# Tractive_System_Active_Light_rev5.net
KiCad netlist of a schematic drawn in EAGLE
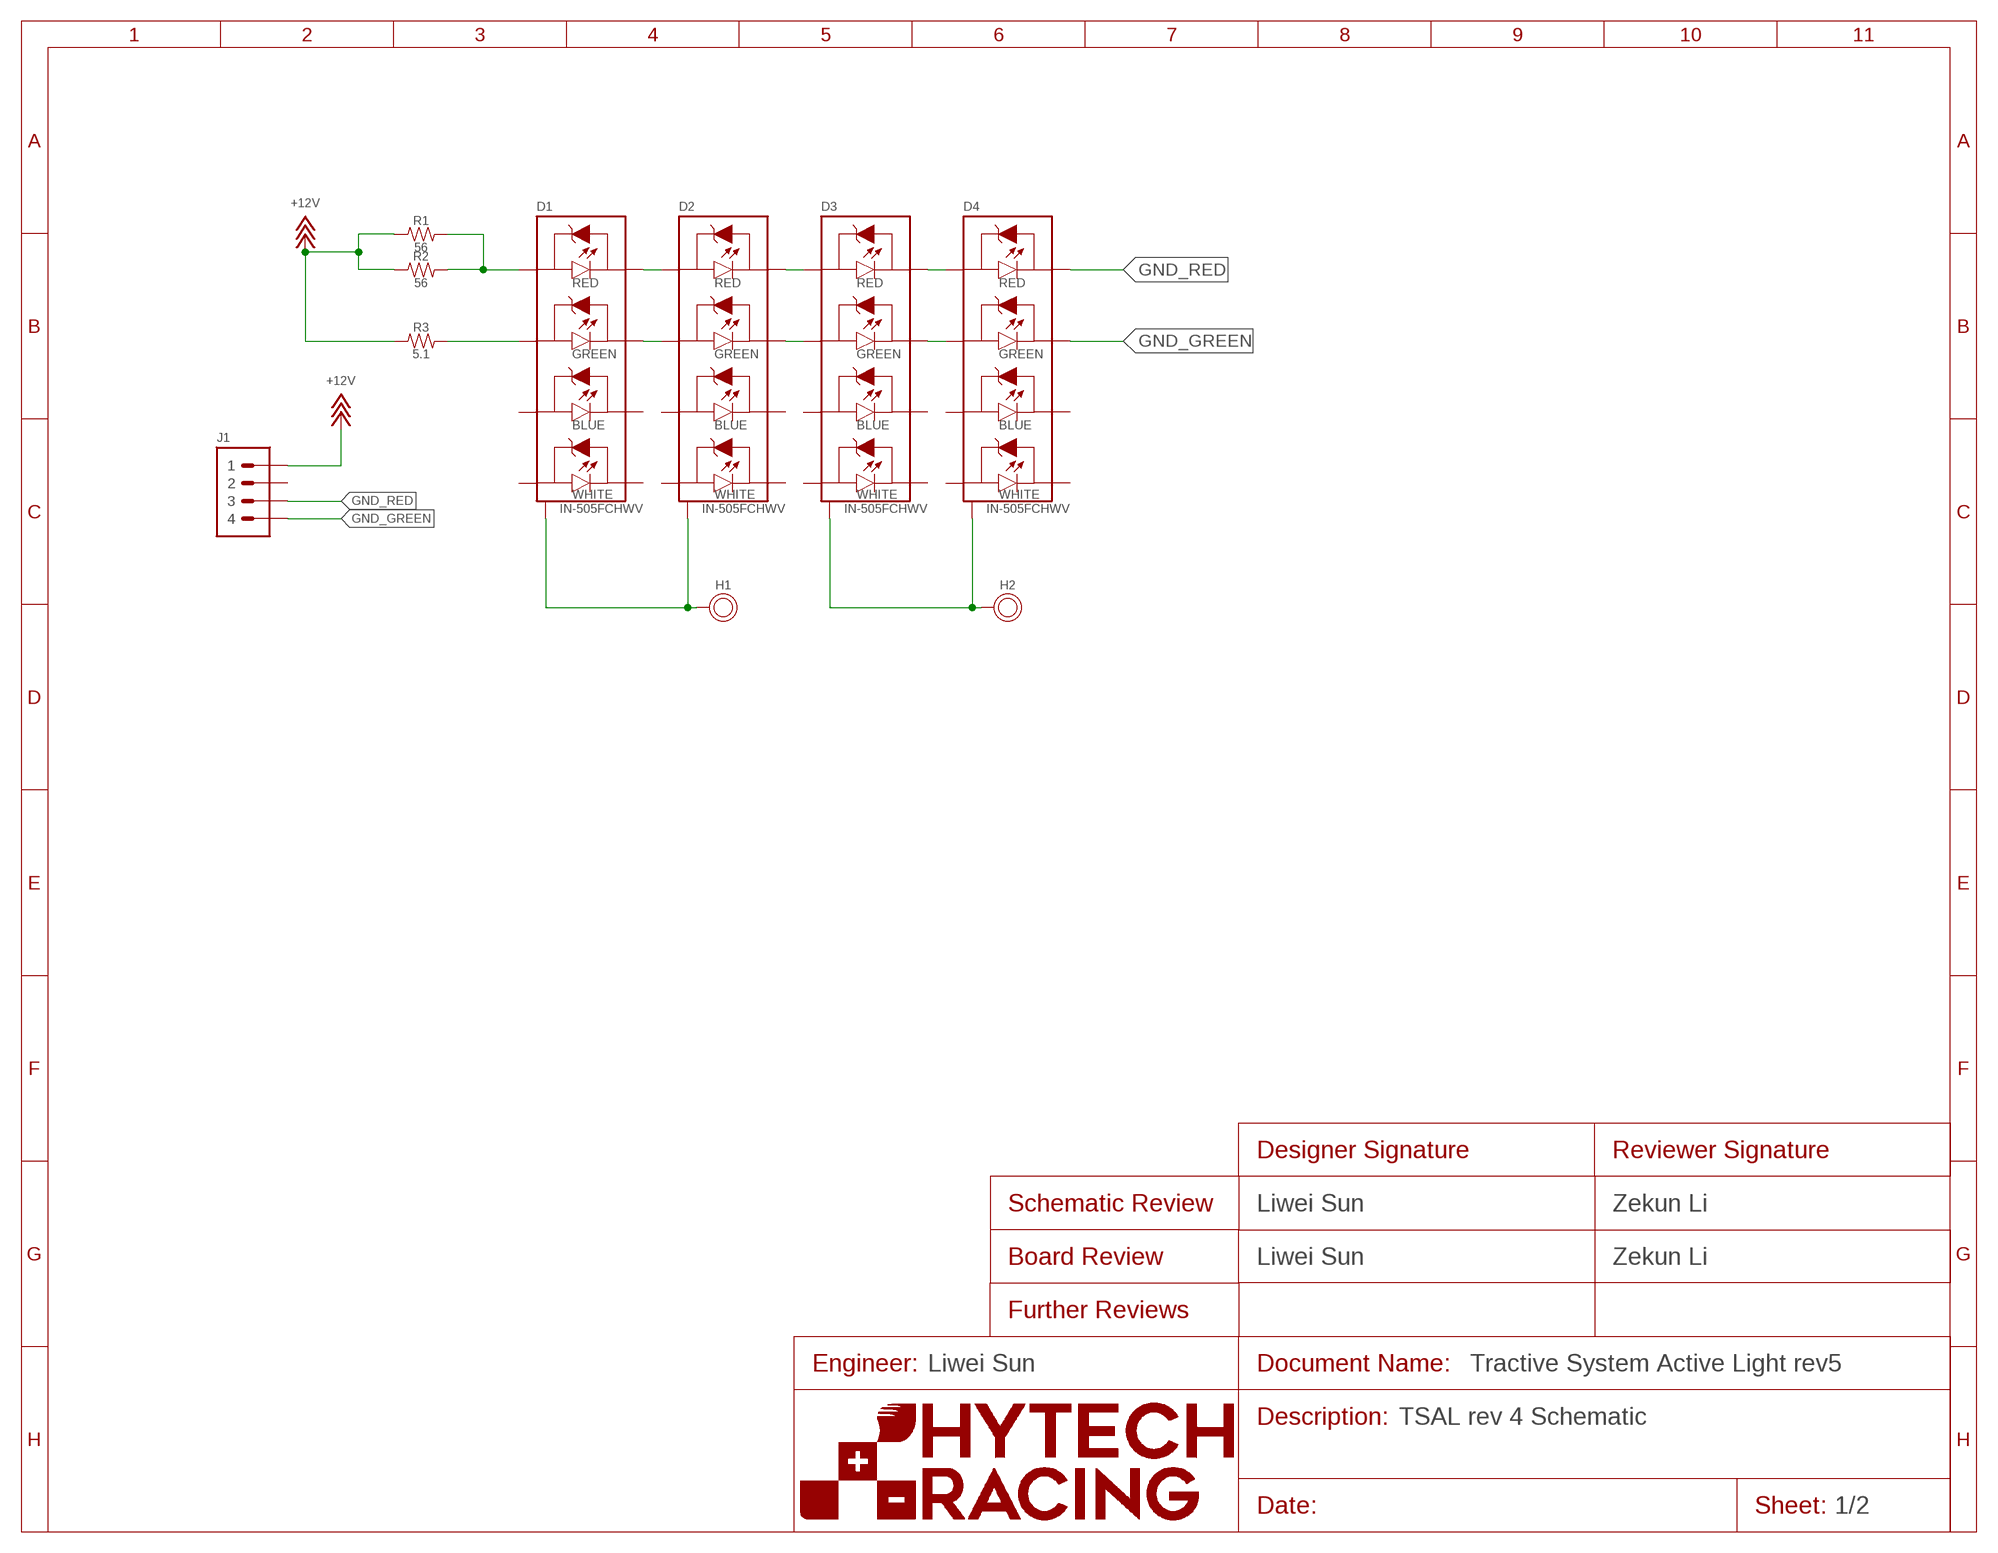
[diagram p0: schematic, sheet 1]
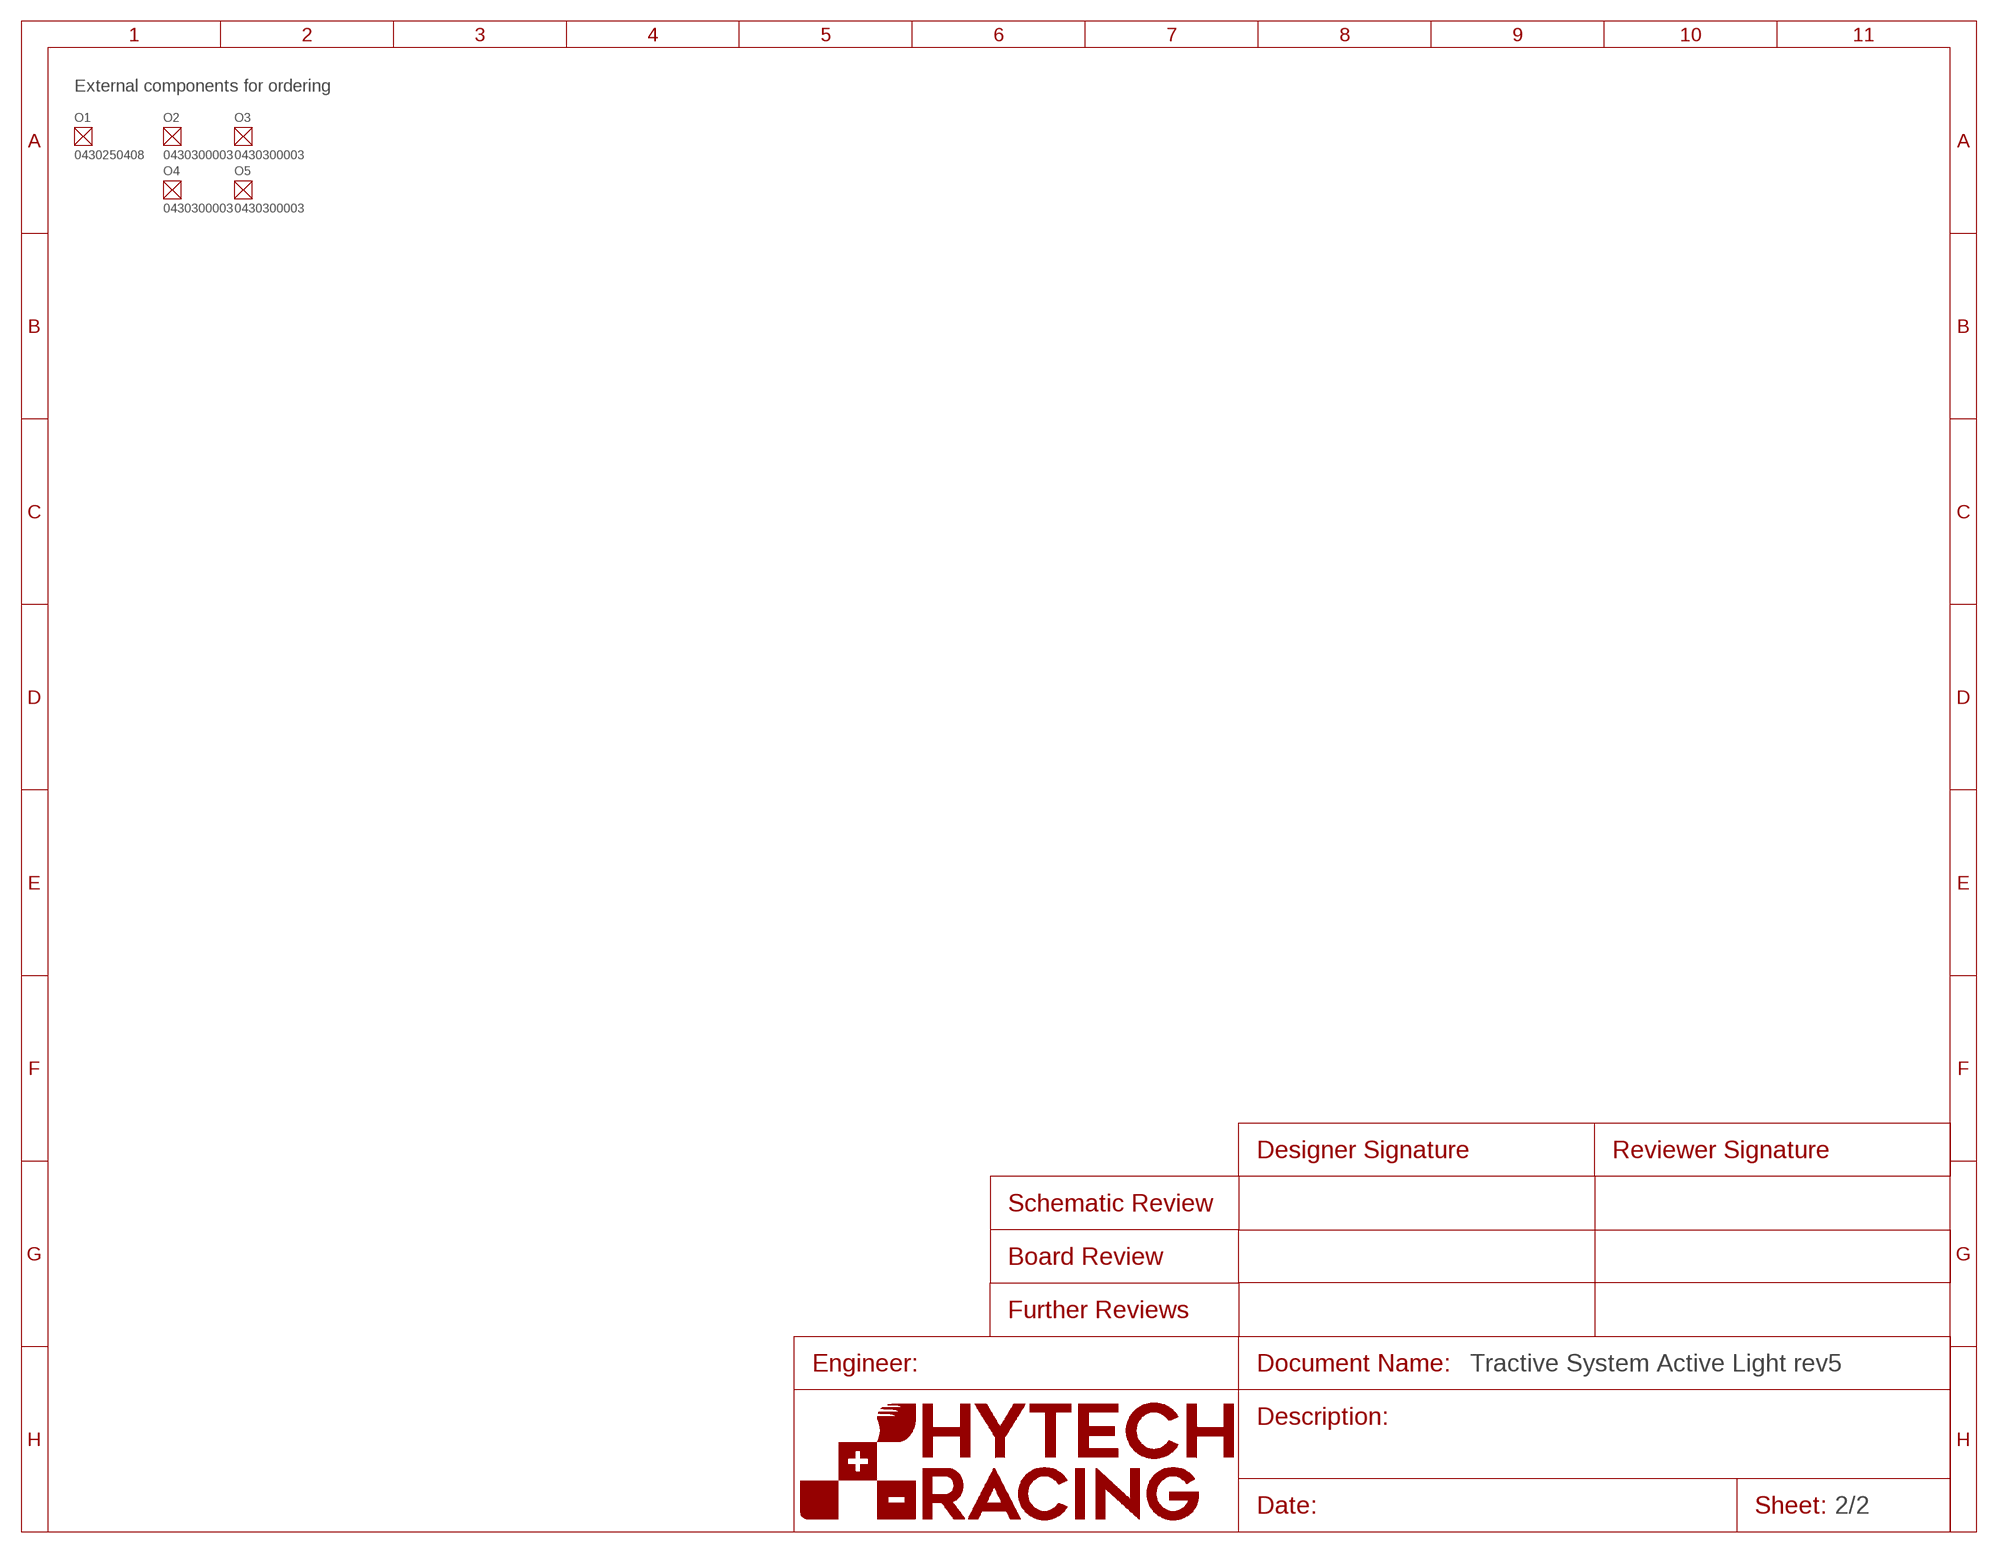
[diagram p1: schematic, sheet 2]

(export (version "E")
  (design (tool "Eeschema 10.0.6"))
  (components
    (comp (ref "D1")
      (value "LED_RGBW_IN-505FCHWV")
      (footprint "eagle-import:IN-505FCHWV")
      (fields (field (name "MPN") "IN-505FCHWV") (field (name "MANUFACTURER") "INOLUX"))
      (libsource (lib "eagle-import") (part "LED_RGBW_IN-505FCHWV"))
    )
    (comp (ref "D2")
      (value "LED_RGBW_IN-505FCHWV")
      (footprint "eagle-import:IN-505FCHWV")
      (fields (field (name "MPN") "IN-505FCHWV") (field (name "MANUFACTURER") "INOLUX"))
      (libsource (lib "eagle-import") (part "LED_RGBW_IN-505FCHWV"))
    )
    (comp (ref "D3")
      (value "LED_RGBW_IN-505FCHWV")
      (footprint "eagle-import:IN-505FCHWV")
      (fields (field (name "MPN") "IN-505FCHWV") (field (name "MANUFACTURER") "INOLUX"))
      (libsource (lib "eagle-import") (part "LED_RGBW_IN-505FCHWV"))
    )
    (comp (ref "D4")
      (value "LED_RGBW_IN-505FCHWV")
      (footprint "eagle-import:IN-505FCHWV")
      (fields (field (name "MPN") "IN-505FCHWV") (field (name "MANUFACTURER") "INOLUX"))
      (libsource (lib "eagle-import") (part "LED_RGBW_IN-505FCHWV"))
    )
    (comp (ref "H1")
      (value "MOUNTING_HEATSINK_M3")
      (footprint "eagle-import:MOUNTING_M3")
      (libsource (lib "eagle-import") (part "MOUNTING_HEATSINK_M3"))
    )
    (comp (ref "H2")
      (value "MOUNTING_HEATSINK_M3")
      (footprint "eagle-import:MOUNTING_M3")
      (libsource (lib "eagle-import") (part "MOUNTING_HEATSINK_M3"))
    )
    (comp (ref "J1")
      (value "CONNECTOR-4_μF_S_RA_")
      (footprint "eagle-import:MOLEX_MICROFIT_SMD_RIGHTANGLE_04_DUAL")
      (fields (field (name "MPN") "0430450411") (field (name "MANUFACTURER") "Molex"))
      (libsource (lib "eagle-import") (part "CONNECTOR-4_?_μF_S_RA"))
    )
    (comp (ref "R1")
      (value "RESISTOR_0805_56")
      (footprint "eagle-import:0805-RES")
      (fields
        (field (name "MANUFACTURER") "Panasonic Electronic Components")
        (field (name "MPN") "ERJ-P06D56R0V")
        (field (name "POWER") "0.5W")
        (field (name "RESISTANCE") "56")
      )
      (libsource (lib "eagle-import") (part "RESISTOR_?_080556"))
    )
    (comp (ref "R2")
      (value "RESISTOR_0805_56")
      (footprint "eagle-import:0805-RES")
      (fields
        (field (name "MANUFACTURER") "Panasonic Electronic Components")
        (field (name "MPN") "ERJ-P06D56R0V")
        (field (name "POWER") "0.5W")
        (field (name "RESISTANCE") "56")
      )
      (libsource (lib "eagle-import") (part "RESISTOR_?_080556"))
    )
    (comp (ref "R3")
      (value "RESISTOR_0603_5.1")
      (footprint "eagle-import:0603-RES")
      (fields
        (field (name "MANUFACTURER") "Panasonic Electronic Components")
        (field (name "MPN") "ERJ-P03J5R1V")
        (field (name "POWER") "0.25W")
        (field (name "RESISTANCE") "5.1")
      )
      (libsource (lib "eagle-import") (part "RESISTOR_?_06035.1"))
    )
  )
  (nets
    (net (code "1") (name "+12V") (class "Default")
      (node (ref "J1") (pin "1") (pinfunction "1_1") (pintype "passive"))
      (node (ref "R1") (pin "1") (pinfunction "1_1") (pintype "passive"))
      (node (ref "R2") (pin "1") (pinfunction "1_1") (pintype "passive"))
      (node (ref "R3") (pin "1") (pinfunction "1_1") (pintype "passive"))
    )
    (net (code "2") (name "GND_GREEN") (class "Default")
      (node (ref "D4") (pin "B-") (pinfunction "GREEN-_B-") (pintype "passive"))
      (node (ref "J1") (pin "4") (pinfunction "4_4") (pintype "passive"))
    )
    (net (code "3") (name "GND_RED") (class "Default")
      (node (ref "D4") (pin "A-") (pinfunction "RED-_A-") (pintype "passive"))
      (node (ref "J1") (pin "3") (pinfunction "3_3") (pintype "passive"))
    )
    (net (code "4") (name "Net-(D1-GREEN+)") (class "Default")
      (node (ref "D1") (pin "B+") (pinfunction "GREEN+_B+") (pintype "passive"))
      (node (ref "R3") (pin "2") (pinfunction "2_2") (pintype "passive"))
    )
    (net (code "5") (name "Net-(D1-GREEN-)") (class "Default")
      (node (ref "D1") (pin "B-") (pinfunction "GREEN-_B-") (pintype "passive"))
      (node (ref "D2") (pin "B+") (pinfunction "GREEN+_B+") (pintype "passive"))
    )
    (net (code "6") (name "Net-(D1-PadTHERMAL)") (class "Default")
      (node (ref "D1") (pin "THERMAL") (pinfunction "THERMAL_THERMAL") (pintype "passive"))
      (node (ref "D2") (pin "THERMAL") (pinfunction "THERMAL_THERMAL") (pintype "passive"))
      (node (ref "H1") (pin "P$1") (pinfunction "P$1_P$1") (pintype "passive"))
    )
    (net (code "7") (name "Net-(D1-RED+)") (class "Default")
      (node (ref "D1") (pin "A+") (pinfunction "RED+_A+") (pintype "passive"))
      (node (ref "R1") (pin "2") (pinfunction "2_2") (pintype "passive"))
      (node (ref "R2") (pin "2") (pinfunction "2_2") (pintype "passive"))
    )
    (net (code "8") (name "Net-(D1-RED-)") (class "Default")
      (node (ref "D1") (pin "A-") (pinfunction "RED-_A-") (pintype "passive"))
      (node (ref "D2") (pin "A+") (pinfunction "RED+_A+") (pintype "passive"))
    )
    (net (code "9") (name "Net-(D2-GREEN-)") (class "Default")
      (node (ref "D2") (pin "B-") (pinfunction "GREEN-_B-") (pintype "passive"))
      (node (ref "D3") (pin "B+") (pinfunction "GREEN+_B+") (pintype "passive"))
    )
    (net (code "10") (name "Net-(D2-RED-)") (class "Default")
      (node (ref "D2") (pin "A-") (pinfunction "RED-_A-") (pintype "passive"))
      (node (ref "D3") (pin "A+") (pinfunction "RED+_A+") (pintype "passive"))
    )
    (net (code "11") (name "Net-(D3-GREEN-)") (class "Default")
      (node (ref "D3") (pin "B-") (pinfunction "GREEN-_B-") (pintype "passive"))
      (node (ref "D4") (pin "B+") (pinfunction "GREEN+_B+") (pintype "passive"))
    )
    (net (code "12") (name "Net-(D3-PadTHERMAL)") (class "Default")
      (node (ref "D3") (pin "THERMAL") (pinfunction "THERMAL_THERMAL") (pintype "passive"))
      (node (ref "D4") (pin "THERMAL") (pinfunction "THERMAL_THERMAL") (pintype "passive"))
      (node (ref "H2") (pin "P$1") (pinfunction "P$1_P$1") (pintype "passive"))
    )
    (net (code "13") (name "Net-(D3-RED-)") (class "Default")
      (node (ref "D3") (pin "A-") (pinfunction "RED-_A-") (pintype "passive"))
      (node (ref "D4") (pin "A+") (pinfunction "RED+_A+") (pintype "passive"))
    )
    (net (code "14") (name "unconnected-(D1-BLUE+-PadC+)") (class "Default")
      (node (ref "D1") (pin "C+") (pinfunction "BLUE+_C+") (pintype "passive"))
    )
    (net (code "15") (name "unconnected-(D1-BLUE--PadC-)") (class "Default")
      (node (ref "D1") (pin "C-") (pinfunction "BLUE-_C-") (pintype "passive"))
    )
    (net (code "16") (name "unconnected-(D1-WHITE+-PadD+)") (class "Default")
      (node (ref "D1") (pin "D+") (pinfunction "WHITE+_D+") (pintype "passive"))
    )
    (net (code "17") (name "unconnected-(D1-WHITE--PadD-)") (class "Default")
      (node (ref "D1") (pin "D-") (pinfunction "WHITE-_D-") (pintype "passive"))
    )
    (net (code "18") (name "unconnected-(D2-BLUE+-PadC+)") (class "Default")
      (node (ref "D2") (pin "C+") (pinfunction "BLUE+_C+") (pintype "passive"))
    )
    (net (code "19") (name "unconnected-(D2-BLUE--PadC-)") (class "Default")
      (node (ref "D2") (pin "C-") (pinfunction "BLUE-_C-") (pintype "passive"))
    )
    (net (code "20") (name "unconnected-(D2-WHITE+-PadD+)") (class "Default")
      (node (ref "D2") (pin "D+") (pinfunction "WHITE+_D+") (pintype "passive"))
    )
    (net (code "21") (name "unconnected-(D2-WHITE--PadD-)") (class "Default")
      (node (ref "D2") (pin "D-") (pinfunction "WHITE-_D-") (pintype "passive"))
    )
    (net (code "22") (name "unconnected-(D3-BLUE+-PadC+)") (class "Default")
      (node (ref "D3") (pin "C+") (pinfunction "BLUE+_C+") (pintype "passive"))
    )
    (net (code "23") (name "unconnected-(D3-BLUE--PadC-)") (class "Default")
      (node (ref "D3") (pin "C-") (pinfunction "BLUE-_C-") (pintype "passive"))
    )
    (net (code "24") (name "unconnected-(D3-WHITE+-PadD+)") (class "Default")
      (node (ref "D3") (pin "D+") (pinfunction "WHITE+_D+") (pintype "passive"))
    )
    (net (code "25") (name "unconnected-(D3-WHITE--PadD-)") (class "Default")
      (node (ref "D3") (pin "D-") (pinfunction "WHITE-_D-") (pintype "passive"))
    )
    (net (code "26") (name "unconnected-(D4-BLUE+-PadC+)") (class "Default")
      (node (ref "D4") (pin "C+") (pinfunction "BLUE+_C+") (pintype "passive"))
    )
    (net (code "27") (name "unconnected-(D4-BLUE--PadC-)") (class "Default")
      (node (ref "D4") (pin "C-") (pinfunction "BLUE-_C-") (pintype "passive"))
    )
    (net (code "28") (name "unconnected-(D4-WHITE+-PadD+)") (class "Default")
      (node (ref "D4") (pin "D+") (pinfunction "WHITE+_D+") (pintype "passive"))
    )
    (net (code "29") (name "unconnected-(D4-WHITE--PadD-)") (class "Default")
      (node (ref "D4") (pin "D-") (pinfunction "WHITE-_D-") (pintype "passive"))
    )
    (net (code "30") (name "unconnected-(J1-Pad2)") (class "Default")
      (node (ref "J1") (pin "2") (pinfunction "2_2") (pintype "passive"))
    )
  )
)
